# antibounce.net
KiCad netlist of a schematic drawn in EAGLE
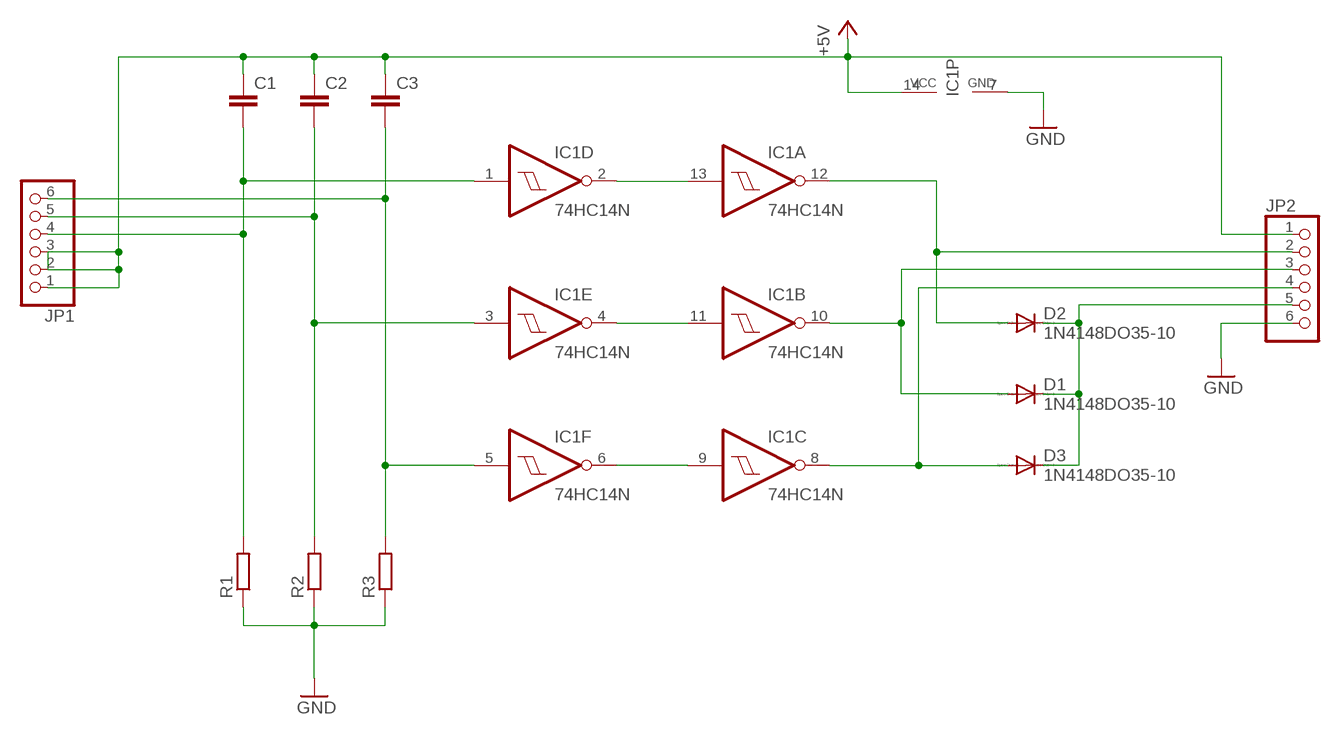
[diagram p0: schematic, sheet 1]

(export (version "E")
  (design (tool "Eeschema 10.0.6"))
  (components
    (comp (ref "C1")
      (value "C-EU050-024X044")
      (footprint "eagle-import:C050-024X044")
      (libsource (lib "eagle-import") (part "C-EU050-024X044"))
    )
    (comp (ref "C2")
      (value "C-EU050-024X044")
      (footprint "eagle-import:C050-024X044")
      (libsource (lib "eagle-import") (part "C-EU050-024X044"))
    )
    (comp (ref "C3")
      (value "C-EU050-024X044")
      (footprint "eagle-import:C050-024X044")
      (libsource (lib "eagle-import") (part "C-EU050-024X044"))
    )
    (comp (ref "D1")
      (value "1N4148DO35-10")
      (footprint "eagle-import:DO35-10")
      (libsource (lib "eagle-import") (part "1N4148DO35-10"))
    )
    (comp (ref "D2")
      (value "1N4148DO35-10")
      (footprint "eagle-import:DO35-10")
      (libsource (lib "eagle-import") (part "1N4148DO35-10"))
    )
    (comp (ref "D3")
      (value "1N4148DO35-10")
      (footprint "eagle-import:DO35-10")
      (libsource (lib "eagle-import") (part "1N4148DO35-10"))
    )
    (comp (ref "IC1")
      (value "74HC14N")
      (footprint "eagle-import:DIL14")
      (libsource (lib "eagle-import") (part "7414NHC"))
    )
    (comp (ref "JP1")
      (value "PINHD-1X6")
      (footprint "eagle-import:1X06")
      (libsource (lib "eagle-import") (part "PINHD-1X6"))
    )
    (comp (ref "JP2")
      (value "PINHD-1X6")
      (footprint "eagle-import:1X06")
      (libsource (lib "eagle-import") (part "PINHD-1X6"))
    )
    (comp (ref "R1")
      (value "R-EU_0207/10")
      (footprint "eagle-import:0207_10")
      (libsource (lib "eagle-import") (part "R-EU_0207/10"))
    )
    (comp (ref "R2")
      (value "R-EU_0207/10")
      (footprint "eagle-import:0207_10")
      (libsource (lib "eagle-import") (part "R-EU_0207/10"))
    )
    (comp (ref "R3")
      (value "R-EU_0207/10")
      (footprint "eagle-import:0207_10")
      (libsource (lib "eagle-import") (part "R-EU_0207/10"))
    )
  )
  (nets
    (net (code "1") (name "+5V") (class "Default")
      (node (ref "C1") (pin "1") (pinfunction "1_1") (pintype "passive"))
      (node (ref "C2") (pin "1") (pinfunction "1_1") (pintype "passive"))
      (node (ref "C3") (pin "1") (pinfunction "1_1") (pintype "passive"))
      (node (ref "IC1") (pin "14") (pinfunction "VCC_14") (pintype "power_in"))
      (node (ref "JP1") (pin "1") (pinfunction "1_1") (pintype "passive"))
      (node (ref "JP1") (pin "2") (pinfunction "2_2") (pintype "passive"))
      (node (ref "JP1") (pin "3") (pinfunction "3_3") (pintype "passive"))
      (node (ref "JP2") (pin "1") (pinfunction "1_1") (pintype "passive"))
    )
    (net (code "2") (name "GND") (class "Default")
      (node (ref "IC1") (pin "7") (pinfunction "GND_7") (pintype "power_in"))
      (node (ref "JP2") (pin "6") (pinfunction "6_6") (pintype "passive"))
      (node (ref "R1") (pin "1") (pinfunction "1_1") (pintype "passive"))
      (node (ref "R2") (pin "1") (pinfunction "1_1") (pintype "passive"))
      (node (ref "R3") (pin "1") (pinfunction "1_1") (pintype "passive"))
    )
    (net (code "3") (name "Net-(D1-PadC)") (class "Default")
      (node (ref "D1") (pin "C") (pinfunction "C_C") (pintype "passive"))
      (node (ref "D2") (pin "C") (pinfunction "C_C") (pintype "passive"))
      (node (ref "D3") (pin "C") (pinfunction "C_C") (pintype "passive"))
      (node (ref "JP2") (pin "5") (pinfunction "5_5") (pintype "passive"))
    )
    (net (code "4") (name "Net-(IC1A-I)") (class "Default")
      (node (ref "IC1") (pin "13") (pinfunction "I_13") (pintype "input"))
      (node (ref "IC1") (pin "2") (pinfunction "O_2") (pintype "output"))
    )
    (net (code "5") (name "Net-(IC1A-O)") (class "Default")
      (node (ref "D2") (pin "A") (pinfunction "A_A") (pintype "passive"))
      (node (ref "IC1") (pin "12") (pinfunction "O_12") (pintype "output"))
      (node (ref "JP2") (pin "2") (pinfunction "2_2") (pintype "passive"))
    )
    (net (code "6") (name "Net-(IC1B-I)") (class "Default")
      (node (ref "IC1") (pin "11") (pinfunction "I_11") (pintype "input"))
      (node (ref "IC1") (pin "4") (pinfunction "O_4") (pintype "output"))
    )
    (net (code "7") (name "Net-(IC1B-O)") (class "Default")
      (node (ref "D1") (pin "A") (pinfunction "A_A") (pintype "passive"))
      (node (ref "IC1") (pin "10") (pinfunction "O_10") (pintype "output"))
      (node (ref "JP2") (pin "3") (pinfunction "3_3") (pintype "passive"))
    )
    (net (code "8") (name "Net-(IC1C-I)") (class "Default")
      (node (ref "IC1") (pin "6") (pinfunction "O_6") (pintype "output"))
      (node (ref "IC1") (pin "9") (pinfunction "I_9") (pintype "input"))
    )
    (net (code "9") (name "Net-(IC1C-O)") (class "Default")
      (node (ref "D3") (pin "A") (pinfunction "A_A") (pintype "passive"))
      (node (ref "IC1") (pin "8") (pinfunction "O_8") (pintype "output"))
      (node (ref "JP2") (pin "4") (pinfunction "4_4") (pintype "passive"))
    )
    (net (code "10") (name "Net-(IC1D-I)") (class "Default")
      (node (ref "C1") (pin "2") (pinfunction "2_2") (pintype "passive"))
      (node (ref "IC1") (pin "1") (pinfunction "I_1") (pintype "input"))
      (node (ref "JP1") (pin "4") (pinfunction "4_4") (pintype "passive"))
      (node (ref "R1") (pin "2") (pinfunction "2_2") (pintype "passive"))
    )
    (net (code "11") (name "Net-(IC1E-I)") (class "Default")
      (node (ref "C2") (pin "2") (pinfunction "2_2") (pintype "passive"))
      (node (ref "IC1") (pin "3") (pinfunction "I_3") (pintype "input"))
      (node (ref "JP1") (pin "5") (pinfunction "5_5") (pintype "passive"))
      (node (ref "R2") (pin "2") (pinfunction "2_2") (pintype "passive"))
    )
    (net (code "12") (name "Net-(IC1F-I)") (class "Default")
      (node (ref "C3") (pin "2") (pinfunction "2_2") (pintype "passive"))
      (node (ref "IC1") (pin "5") (pinfunction "I_5") (pintype "input"))
      (node (ref "JP1") (pin "6") (pinfunction "6_6") (pintype "passive"))
      (node (ref "R3") (pin "2") (pinfunction "2_2") (pintype "passive"))
    )
  )
)
